# RACOON.net
KiCad netlist of a schematic drawn in EAGLE
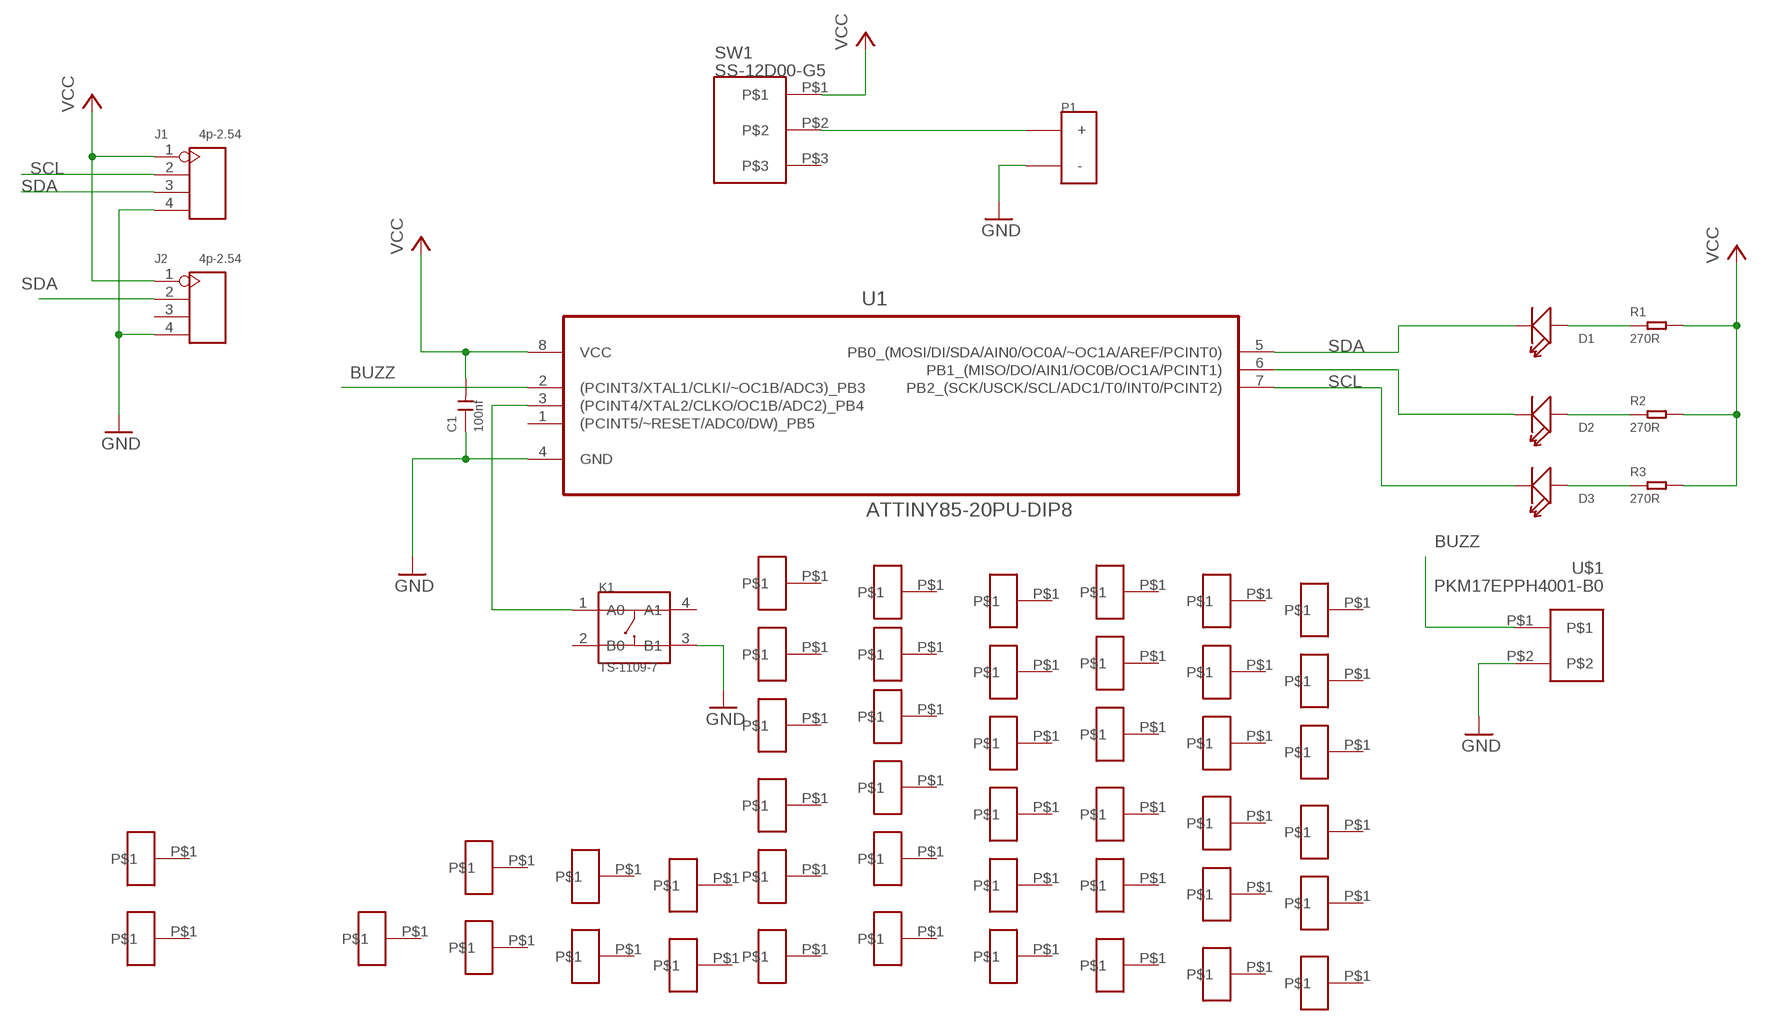
[diagram p0: schematic, sheet 1]

(export (version "E")
  (design (tool "Eeschema 10.0.6"))
  (components
    (comp (ref "C1")
      (value "100nf")
      (footprint "eagle-import:CERAMIC-2.54")
      (fields (field (name "MPN") "CC1-F5SL2A101KSPW"))
      (libsource (lib "eagle-import") (part "DIP-CERAMIC-DISC-100NF-50V-Y5V(D5.0MM)"))
    )
    (comp (ref "D1")
      (value "504BW")
      (footprint "eagle-import:LED2-2.54-D5.0MM")
      (libsource (lib "eagle-import") (part "DIP-LED-BLUE-BLUE(2P-D5MM)"))
    )
    (comp (ref "D2")
      (value "504BW")
      (footprint "eagle-import:LED2-2.54-D5.0MM")
      (libsource (lib "eagle-import") (part "DIP-LED-BLUE-BLUE(2P-D5MM)"))
    )
    (comp (ref "D3")
      (value "504BW")
      (footprint "eagle-import:LED2-2.54-D5.0MM")
      (libsource (lib "eagle-import") (part "DIP-LED-BLUE-BLUE(2P-D5MM)"))
    )
    (comp (ref "J1")
      (value "4p-2.54")
      (footprint "eagle-import:H4-2.54")
      (fields (field (name "MPN") "F185-1104A1BSYA1"))
      (libsource (lib "eagle-import") (part "DIP-BLACK-FEMALE-HEADER-VERT(4P-2.54)"))
    )
    (comp (ref "J2")
      (value "4p-2.54")
      (footprint "eagle-import:H4-2.54")
      (fields (field (name "MPN") "F185-1104A1BSYA1"))
      (libsource (lib "eagle-import") (part "DIP-BLACK-FEMALE-HEADER-VERT(4P-2.54)"))
    )
    (comp (ref "K1")
      (value "TS-1109-7")
      (footprint "eagle-import:SW4-6.2X6.2X5.0MM")
      (libsource (lib "eagle-import") (part "DIP-BUTTON-TOP-BLACK(4P-D6.2MM)"))
    )
    (comp (ref "P1")
      (value "BATTERY")
      (footprint "eagle-import:BAT_CR2450_TH_BS2450")
      (libsource (lib "eagle-import") (part "BATTERY"))
    )
    (comp (ref "R1")
      (value "270R")
      (footprint "eagle-import:PR-D2.3XL6.5MM")
      (fields (field (name "MPN") "FHCFR-1/4W-271J"))
      (libsource (lib "eagle-import") (part "DIP-RES-270R-5%-1/4W(PR-D2.3XL6.5MM)"))
    )
    (comp (ref "R2")
      (value "270R")
      (footprint "eagle-import:PR-D2.3XL6.5MM")
      (fields (field (name "MPN") "FHCFR-1/4W-271J"))
      (libsource (lib "eagle-import") (part "DIP-RES-270R-5%-1/4W(PR-D2.3XL6.5MM)"))
    )
    (comp (ref "R3")
      (value "270R")
      (footprint "eagle-import:PR-D2.3XL6.5MM")
      (fields (field (name "MPN") "FHCFR-1/4W-271J"))
      (libsource (lib "eagle-import") (part "DIP-RES-270R-5%-1/4W(PR-D2.3XL6.5MM)"))
    )
    (comp (ref "SW1")
      (value "SS-12D00-G5")
      (footprint "eagle-import:SS-12D00-G5")
      (libsource (lib "eagle-import") (part "SS-12D00-G5"))
    )
    (comp (ref "U$1")
      (value "PKM17EPPH4001-B0")
      (footprint "eagle-import:PKM17EPPH4001-B0")
      (libsource (lib "eagle-import") (part "PKM17EPPH4001-B0"))
    )
    (comp (ref "U$2")
      (value "1PIN_HOLE")
      (footprint "eagle-import:1PIN_HOLE")
      (libsource (lib "eagle-import") (part "1PIN_HOLE"))
    )
    (comp (ref "U$3")
      (value "1PIN_HOLE")
      (footprint "eagle-import:1PIN_HOLE")
      (libsource (lib "eagle-import") (part "1PIN_HOLE"))
    )
    (comp (ref "U$4")
      (value "1PIN_HOLE")
      (footprint "eagle-import:1PIN_HOLE")
      (libsource (lib "eagle-import") (part "1PIN_HOLE"))
    )
    (comp (ref "U$5")
      (value "1PIN_HOLE")
      (footprint "eagle-import:1PIN_HOLE")
      (libsource (lib "eagle-import") (part "1PIN_HOLE"))
    )
    (comp (ref "U$6")
      (value "1PIN_HOLE")
      (footprint "eagle-import:1PIN_HOLE")
      (libsource (lib "eagle-import") (part "1PIN_HOLE"))
    )
    (comp (ref "U$7")
      (value "1PIN_HOLE")
      (footprint "eagle-import:1PIN_HOLE")
      (libsource (lib "eagle-import") (part "1PIN_HOLE"))
    )
    (comp (ref "U$8")
      (value "1PIN_HOLE")
      (footprint "eagle-import:1PIN_HOLE")
      (libsource (lib "eagle-import") (part "1PIN_HOLE"))
    )
    (comp (ref "U$9")
      (value "1PIN_HOLE")
      (footprint "eagle-import:1PIN_HOLE")
      (libsource (lib "eagle-import") (part "1PIN_HOLE"))
    )
    (comp (ref "U$10")
      (value "1PIN_HOLE")
      (footprint "eagle-import:1PIN_HOLE")
      (libsource (lib "eagle-import") (part "1PIN_HOLE"))
    )
    (comp (ref "U$11")
      (value "1PIN_HOLE")
      (footprint "eagle-import:1PIN_HOLE")
      (libsource (lib "eagle-import") (part "1PIN_HOLE"))
    )
    (comp (ref "U$12")
      (value "1PIN_HOLE")
      (footprint "eagle-import:1PIN_HOLE")
      (libsource (lib "eagle-import") (part "1PIN_HOLE"))
    )
    (comp (ref "U$13")
      (value "1PIN_HOLE")
      (footprint "eagle-import:1PIN_HOLE")
      (libsource (lib "eagle-import") (part "1PIN_HOLE"))
    )
    (comp (ref "U$14")
      (value "1PIN_HOLE")
      (footprint "eagle-import:1PIN_HOLE")
      (libsource (lib "eagle-import") (part "1PIN_HOLE"))
    )
    (comp (ref "U$15")
      (value "1PIN_HOLE")
      (footprint "eagle-import:1PIN_HOLE")
      (libsource (lib "eagle-import") (part "1PIN_HOLE"))
    )
    (comp (ref "U$16")
      (value "1PIN_HOLE")
      (footprint "eagle-import:1PIN_HOLE")
      (libsource (lib "eagle-import") (part "1PIN_HOLE"))
    )
    (comp (ref "U$17")
      (value "1PIN_HOLE")
      (footprint "eagle-import:1PIN_HOLE")
      (libsource (lib "eagle-import") (part "1PIN_HOLE"))
    )
    (comp (ref "U$18")
      (value "1PIN_HOLE")
      (footprint "eagle-import:1PIN_HOLE")
      (libsource (lib "eagle-import") (part "1PIN_HOLE"))
    )
    (comp (ref "U$19")
      (value "1PIN_HOLE")
      (footprint "eagle-import:1PIN_HOLE")
      (libsource (lib "eagle-import") (part "1PIN_HOLE"))
    )
    (comp (ref "U$20")
      (value "1PIN_HOLE")
      (footprint "eagle-import:1PIN_HOLE")
      (libsource (lib "eagle-import") (part "1PIN_HOLE"))
    )
    (comp (ref "U$21")
      (value "1PIN_HOLE")
      (footprint "eagle-import:1PIN_HOLE")
      (libsource (lib "eagle-import") (part "1PIN_HOLE"))
    )
    (comp (ref "U$22")
      (value "1PIN_HOLE")
      (footprint "eagle-import:1PIN_HOLE")
      (libsource (lib "eagle-import") (part "1PIN_HOLE"))
    )
    (comp (ref "U$23")
      (value "1PIN_HOLE")
      (footprint "eagle-import:1PIN_HOLE")
      (libsource (lib "eagle-import") (part "1PIN_HOLE"))
    )
    (comp (ref "U$24")
      (value "1PIN_HOLE")
      (footprint "eagle-import:1PIN_HOLE")
      (libsource (lib "eagle-import") (part "1PIN_HOLE"))
    )
    (comp (ref "U$25")
      (value "1PIN_HOLE")
      (footprint "eagle-import:1PIN_HOLE")
      (libsource (lib "eagle-import") (part "1PIN_HOLE"))
    )
    (comp (ref "U$26")
      (value "1PIN_HOLE")
      (footprint "eagle-import:1PIN_HOLE")
      (libsource (lib "eagle-import") (part "1PIN_HOLE"))
    )
    (comp (ref "U$27")
      (value "1PIN_HOLE")
      (footprint "eagle-import:1PIN_HOLE")
      (libsource (lib "eagle-import") (part "1PIN_HOLE"))
    )
    (comp (ref "U$28")
      (value "1PIN_HOLE")
      (footprint "eagle-import:1PIN_HOLE")
      (libsource (lib "eagle-import") (part "1PIN_HOLE"))
    )
    (comp (ref "U$29")
      (value "1PIN_HOLE")
      (footprint "eagle-import:1PIN_HOLE")
      (libsource (lib "eagle-import") (part "1PIN_HOLE"))
    )
    (comp (ref "U$30")
      (value "1PIN_HOLE")
      (footprint "eagle-import:1PIN_HOLE")
      (libsource (lib "eagle-import") (part "1PIN_HOLE"))
    )
    (comp (ref "U$31")
      (value "1PIN_HOLE")
      (footprint "eagle-import:1PIN_HOLE")
      (libsource (lib "eagle-import") (part "1PIN_HOLE"))
    )
    (comp (ref "U$32")
      (value "1PIN_HOLE")
      (footprint "eagle-import:1PIN_HOLE")
      (libsource (lib "eagle-import") (part "1PIN_HOLE"))
    )
    (comp (ref "U$33")
      (value "1PIN_HOLE")
      (footprint "eagle-import:1PIN_HOLE")
      (libsource (lib "eagle-import") (part "1PIN_HOLE"))
    )
    (comp (ref "U$34")
      (value "1PIN_HOLE")
      (footprint "eagle-import:1PIN_HOLE")
      (libsource (lib "eagle-import") (part "1PIN_HOLE"))
    )
    (comp (ref "U$35")
      (value "1PIN_HOLE")
      (footprint "eagle-import:1PIN_HOLE")
      (libsource (lib "eagle-import") (part "1PIN_HOLE"))
    )
    (comp (ref "U$36")
      (value "1PIN_HOLE")
      (footprint "eagle-import:1PIN_HOLE")
      (libsource (lib "eagle-import") (part "1PIN_HOLE"))
    )
    (comp (ref "U$37")
      (value "1PIN_HOLE")
      (footprint "eagle-import:1PIN_HOLE")
      (libsource (lib "eagle-import") (part "1PIN_HOLE"))
    )
    (comp (ref "U$41")
      (value "1PIN_HOLE")
      (footprint "eagle-import:1PIN_HOLE")
      (libsource (lib "eagle-import") (part "1PIN_HOLE"))
    )
    (comp (ref "U$42")
      (value "1PIN_HOLE")
      (footprint "eagle-import:1PIN_HOLE")
      (libsource (lib "eagle-import") (part "1PIN_HOLE"))
    )
    (comp (ref "U$43")
      (value "1PIN_HOLE")
      (footprint "eagle-import:1PIN_HOLE")
      (libsource (lib "eagle-import") (part "1PIN_HOLE"))
    )
    (comp (ref "U$44")
      (value "1PIN_HOLE")
      (footprint "eagle-import:1PIN_HOLE")
      (libsource (lib "eagle-import") (part "1PIN_HOLE"))
    )
    (comp (ref "U$45")
      (value "1PIN_HOLE")
      (footprint "eagle-import:1PIN_HOLE")
      (libsource (lib "eagle-import") (part "1PIN_HOLE"))
    )
    (comp (ref "U$46")
      (value "1PIN_HOLE")
      (footprint "eagle-import:1PIN_HOLE")
      (libsource (lib "eagle-import") (part "1PIN_HOLE"))
    )
    (comp (ref "U$47")
      (value "1PIN_HOLE")
      (footprint "eagle-import:1PIN_HOLE")
      (libsource (lib "eagle-import") (part "1PIN_HOLE"))
    )
    (comp (ref "U$49")
      (value "1PIN_HOLE")
      (footprint "eagle-import:1PIN_HOLE")
      (libsource (lib "eagle-import") (part "1PIN_HOLE"))
    )
    (comp (ref "U$50")
      (value "1PIN_HOLE")
      (footprint "eagle-import:1PIN_HOLE")
      (libsource (lib "eagle-import") (part "1PIN_HOLE"))
    )
    (comp (ref "U1")
      (value "ATTINY85-20PU-DIP8")
      (footprint "eagle-import:DIP254P762X533-8")
      (fields (field (name "MPN") "ATTINY85-20PU"))
      (libsource (lib "eagle-import") (part "MCU-ATTINY85-20PU(DIP8)1"))
    )
  )
  (nets
    (net (code "1") (name "/BUZZ") (class "Default")
      (node (ref "U$1") (pin "P$1") (pinfunction "P$1_P$1") (pintype "bidirectional"))
      (node (ref "U1") (pin "2") (pinfunction "(PCINT3/XTAL1/CLKI/~{OC1B/ADC3})_PB3_2") (pintype "bidirectional"))
    )
    (net (code "2") (name "/SCL") (class "Default")
      (node (ref "D3") (pin "-") (pinfunction "-_-") (pintype "passive"))
      (node (ref "J1") (pin "2") (pinfunction "P$2_2") (pintype "bidirectional"))
      (node (ref "U1") (pin "7") (pinfunction "PB2_(SCK/USCK/SCL/ADC1/T0/INT0/PCINT2)_7") (pintype "bidirectional"))
    )
    (net (code "3") (name "/SDA") (class "Default")
      (node (ref "D1") (pin "-") (pinfunction "-_-") (pintype "passive"))
      (node (ref "J1") (pin "3") (pinfunction "P$3_3") (pintype "bidirectional"))
      (node (ref "J2") (pin "2") (pinfunction "P$2_2") (pintype "bidirectional"))
      (node (ref "U1") (pin "5") (pinfunction "PB0_(MOSI/DI/SDA/AIN0/OC0A/~{OC1A/AREF/PCINT0})_5") (pintype "bidirectional"))
    )
    (net (code "4") (name "GND") (class "Default")
      (node (ref "C1") (pin "1") (pinfunction "1_1") (pintype "passive"))
      (node (ref "J1") (pin "4") (pinfunction "P$4_4") (pintype "bidirectional"))
      (node (ref "J2") (pin "4") (pinfunction "P$4_4") (pintype "bidirectional"))
      (node (ref "K1") (pin "3") (pinfunction "B1_3") (pintype "bidirectional"))
      (node (ref "P1") (pin "-") (pinfunction "-_-") (pintype "power_in"))
      (node (ref "U$1") (pin "P$2") (pinfunction "P$2_P$2") (pintype "bidirectional"))
      (node (ref "U1") (pin "4") (pinfunction "GND_4") (pintype "passive"))
    )
    (net (code "5") (name "Net-(D1-Pad+)") (class "Default")
      (node (ref "D1") (pin "+") (pinfunction "+_+") (pintype "passive"))
      (node (ref "R1") (pin "1") (pinfunction "1_1") (pintype "passive"))
    )
    (net (code "6") (name "Net-(D2-Pad+)") (class "Default")
      (node (ref "D2") (pin "+") (pinfunction "+_+") (pintype "passive"))
      (node (ref "R2") (pin "1") (pinfunction "1_1") (pintype "passive"))
    )
    (net (code "7") (name "Net-(D3-Pad+)") (class "Default")
      (node (ref "D3") (pin "+") (pinfunction "+_+") (pintype "passive"))
      (node (ref "R3") (pin "1") (pinfunction "1_1") (pintype "passive"))
    )
    (net (code "8") (name "Net-(K1-A0)") (class "Default")
      (node (ref "K1") (pin "1") (pinfunction "A0_1") (pintype "bidirectional"))
      (node (ref "U1") (pin "3") (pinfunction "(PCINT4/XTAL2/CLKO/OC1B/ADC2)_PB4_3") (pintype "bidirectional"))
    )
    (net (code "9") (name "Net-(P1-Pad+)") (class "Default")
      (node (ref "P1") (pin "+") (pinfunction "+_+") (pintype "power_in"))
      (node (ref "SW1") (pin "P$2") (pinfunction "P$2_P$2") (pintype "bidirectional"))
    )
    (net (code "10") (name "Net-(U1-PB1_(MISO{slash}DO{slash}AIN1{slash}OC0B{slash}OC1A{slash}PCINT1))") (class "Default")
      (node (ref "D2") (pin "-") (pinfunction "-_-") (pintype "passive"))
      (node (ref "U1") (pin "6") (pinfunction "PB1_(MISO/DO/AIN1/OC0B/OC1A/PCINT1)_6") (pintype "bidirectional"))
    )
    (net (code "11") (name "VCC") (class "Default")
      (node (ref "C1") (pin "2") (pinfunction "2_2") (pintype "passive"))
      (node (ref "J1") (pin "1") (pinfunction "P$1_1") (pintype "bidirectional"))
      (node (ref "J2") (pin "1") (pinfunction "P$1_1") (pintype "bidirectional"))
      (node (ref "R1") (pin "2") (pinfunction "2_2") (pintype "passive"))
      (node (ref "R2") (pin "2") (pinfunction "2_2") (pintype "passive"))
      (node (ref "R3") (pin "2") (pinfunction "2_2") (pintype "passive"))
      (node (ref "SW1") (pin "P$1") (pinfunction "P$1_P$1") (pintype "bidirectional"))
      (node (ref "U1") (pin "8") (pinfunction "VCC_8") (pintype "power_in"))
    )
    (net (code "12") (name "unconnected-(J2-P$3-Pad3)") (class "Default")
      (node (ref "J2") (pin "3") (pinfunction "P$3_3") (pintype "bidirectional"))
    )
    (net (code "13") (name "unconnected-(K1-A1-Pad4)") (class "Default")
      (node (ref "K1") (pin "4") (pinfunction "A1_4") (pintype "bidirectional"))
    )
    (net (code "14") (name "unconnected-(K1-B0-Pad2)") (class "Default")
      (node (ref "K1") (pin "2") (pinfunction "B0_2") (pintype "bidirectional"))
    )
    (net (code "15") (name "unconnected-(SW1-PadP$3)") (class "Default")
      (node (ref "SW1") (pin "P$3") (pinfunction "P$3_P$3") (pintype "bidirectional"))
    )
    (net (code "16") (name "unconnected-(U$2-PadP$1)") (class "Default")
      (node (ref "U$2") (pin "P$1") (pinfunction "P$1_P$1") (pintype "bidirectional"))
    )
    (net (code "17") (name "unconnected-(U$3-PadP$1)") (class "Default")
      (node (ref "U$3") (pin "P$1") (pinfunction "P$1_P$1") (pintype "bidirectional"))
    )
    (net (code "18") (name "unconnected-(U$4-PadP$1)") (class "Default")
      (node (ref "U$4") (pin "P$1") (pinfunction "P$1_P$1") (pintype "bidirectional"))
    )
    (net (code "19") (name "unconnected-(U$5-PadP$1)") (class "Default")
      (node (ref "U$5") (pin "P$1") (pinfunction "P$1_P$1") (pintype "bidirectional"))
    )
    (net (code "20") (name "unconnected-(U$6-PadP$1)") (class "Default")
      (node (ref "U$6") (pin "P$1") (pinfunction "P$1_P$1") (pintype "bidirectional"))
    )
    (net (code "21") (name "unconnected-(U$7-PadP$1)") (class "Default")
      (node (ref "U$7") (pin "P$1") (pinfunction "P$1_P$1") (pintype "bidirectional"))
    )
    (net (code "22") (name "unconnected-(U$8-PadP$1)") (class "Default")
      (node (ref "U$8") (pin "P$1") (pinfunction "P$1_P$1") (pintype "bidirectional"))
    )
    (net (code "23") (name "unconnected-(U$9-PadP$1)") (class "Default")
      (node (ref "U$9") (pin "P$1") (pinfunction "P$1_P$1") (pintype "bidirectional"))
    )
    (net (code "24") (name "unconnected-(U$10-PadP$1)") (class "Default")
      (node (ref "U$10") (pin "P$1") (pinfunction "P$1_P$1") (pintype "bidirectional"))
    )
    (net (code "25") (name "unconnected-(U$11-PadP$1)") (class "Default")
      (node (ref "U$11") (pin "P$1") (pinfunction "P$1_P$1") (pintype "bidirectional"))
    )
    (net (code "26") (name "unconnected-(U$12-PadP$1)") (class "Default")
      (node (ref "U$12") (pin "P$1") (pinfunction "P$1_P$1") (pintype "bidirectional"))
    )
    (net (code "27") (name "unconnected-(U$13-PadP$1)") (class "Default")
      (node (ref "U$13") (pin "P$1") (pinfunction "P$1_P$1") (pintype "bidirectional"))
    )
    (net (code "28") (name "unconnected-(U$14-PadP$1)") (class "Default")
      (node (ref "U$14") (pin "P$1") (pinfunction "P$1_P$1") (pintype "bidirectional"))
    )
    (net (code "29") (name "unconnected-(U$15-PadP$1)") (class "Default")
      (node (ref "U$15") (pin "P$1") (pinfunction "P$1_P$1") (pintype "bidirectional"))
    )
    (net (code "30") (name "unconnected-(U$16-PadP$1)") (class "Default")
      (node (ref "U$16") (pin "P$1") (pinfunction "P$1_P$1") (pintype "bidirectional"))
    )
    (net (code "31") (name "unconnected-(U$17-PadP$1)") (class "Default")
      (node (ref "U$17") (pin "P$1") (pinfunction "P$1_P$1") (pintype "bidirectional"))
    )
    (net (code "32") (name "unconnected-(U$18-PadP$1)") (class "Default")
      (node (ref "U$18") (pin "P$1") (pinfunction "P$1_P$1") (pintype "bidirectional"))
    )
    (net (code "33") (name "unconnected-(U$19-PadP$1)") (class "Default")
      (node (ref "U$19") (pin "P$1") (pinfunction "P$1_P$1") (pintype "bidirectional"))
    )
    (net (code "34") (name "unconnected-(U$20-PadP$1)") (class "Default")
      (node (ref "U$20") (pin "P$1") (pinfunction "P$1_P$1") (pintype "bidirectional"))
    )
    (net (code "35") (name "unconnected-(U$21-PadP$1)") (class "Default")
      (node (ref "U$21") (pin "P$1") (pinfunction "P$1_P$1") (pintype "bidirectional"))
    )
    (net (code "36") (name "unconnected-(U$22-PadP$1)") (class "Default")
      (node (ref "U$22") (pin "P$1") (pinfunction "P$1_P$1") (pintype "bidirectional"))
    )
    (net (code "37") (name "unconnected-(U$23-PadP$1)") (class "Default")
      (node (ref "U$23") (pin "P$1") (pinfunction "P$1_P$1") (pintype "bidirectional"))
    )
    (net (code "38") (name "unconnected-(U$24-PadP$1)") (class "Default")
      (node (ref "U$24") (pin "P$1") (pinfunction "P$1_P$1") (pintype "bidirectional"))
    )
    (net (code "39") (name "unconnected-(U$25-PadP$1)") (class "Default")
      (node (ref "U$25") (pin "P$1") (pinfunction "P$1_P$1") (pintype "bidirectional"))
    )
    (net (code "40") (name "unconnected-(U$26-PadP$1)") (class "Default")
      (node (ref "U$26") (pin "P$1") (pinfunction "P$1_P$1") (pintype "bidirectional"))
    )
    (net (code "41") (name "unconnected-(U$27-PadP$1)") (class "Default")
      (node (ref "U$27") (pin "P$1") (pinfunction "P$1_P$1") (pintype "bidirectional"))
    )
    (net (code "42") (name "unconnected-(U$28-PadP$1)") (class "Default")
      (node (ref "U$28") (pin "P$1") (pinfunction "P$1_P$1") (pintype "bidirectional"))
    )
    (net (code "43") (name "unconnected-(U$29-PadP$1)") (class "Default")
      (node (ref "U$29") (pin "P$1") (pinfunction "P$1_P$1") (pintype "bidirectional"))
    )
    (net (code "44") (name "unconnected-(U$30-PadP$1)") (class "Default")
      (node (ref "U$30") (pin "P$1") (pinfunction "P$1_P$1") (pintype "bidirectional"))
    )
    (net (code "45") (name "unconnected-(U$31-PadP$1)") (class "Default")
      (node (ref "U$31") (pin "P$1") (pinfunction "P$1_P$1") (pintype "bidirectional"))
    )
    (net (code "46") (name "unconnected-(U$32-PadP$1)") (class "Default")
      (node (ref "U$32") (pin "P$1") (pinfunction "P$1_P$1") (pintype "bidirectional"))
    )
    (net (code "47") (name "unconnected-(U$33-PadP$1)") (class "Default")
      (node (ref "U$33") (pin "P$1") (pinfunction "P$1_P$1") (pintype "bidirectional"))
    )
    (net (code "48") (name "unconnected-(U$34-PadP$1)") (class "Default")
      (node (ref "U$34") (pin "P$1") (pinfunction "P$1_P$1") (pintype "bidirectional"))
    )
    (net (code "49") (name "unconnected-(U$35-PadP$1)") (class "Default")
      (node (ref "U$35") (pin "P$1") (pinfunction "P$1_P$1") (pintype "bidirectional"))
    )
    (net (code "50") (name "unconnected-(U$36-PadP$1)") (class "Default")
      (node (ref "U$36") (pin "P$1") (pinfunction "P$1_P$1") (pintype "bidirectional"))
    )
    (net (code "51") (name "unconnected-(U$37-PadP$1)") (class "Default")
      (node (ref "U$37") (pin "P$1") (pinfunction "P$1_P$1") (pintype "bidirectional"))
    )
    (net (code "52") (name "unconnected-(U$41-PadP$1)") (class "Default")
      (node (ref "U$41") (pin "P$1") (pinfunction "P$1_P$1") (pintype "bidirectional"))
    )
    (net (code "53") (name "unconnected-(U$42-PadP$1)") (class "Default")
      (node (ref "U$42") (pin "P$1") (pinfunction "P$1_P$1") (pintype "bidirectional"))
    )
    (net (code "54") (name "unconnected-(U$43-PadP$1)") (class "Default")
      (node (ref "U$43") (pin "P$1") (pinfunction "P$1_P$1") (pintype "bidirectional"))
    )
    (net (code "55") (name "unconnected-(U$44-PadP$1)") (class "Default")
      (node (ref "U$44") (pin "P$1") (pinfunction "P$1_P$1") (pintype "bidirectional"))
    )
    (net (code "56") (name "unconnected-(U$45-PadP$1)") (class "Default")
      (node (ref "U$45") (pin "P$1") (pinfunction "P$1_P$1") (pintype "bidirectional"))
    )
    (net (code "57") (name "unconnected-(U$46-PadP$1)") (class "Default")
      (node (ref "U$46") (pin "P$1") (pinfunction "P$1_P$1") (pintype "bidirectional"))
    )
    (net (code "58") (name "unconnected-(U$47-PadP$1)") (class "Default")
      (node (ref "U$47") (pin "P$1") (pinfunction "P$1_P$1") (pintype "bidirectional"))
    )
    (net (code "59") (name "unconnected-(U$49-PadP$1)") (class "Default")
      (node (ref "U$49") (pin "P$1") (pinfunction "P$1_P$1") (pintype "bidirectional"))
    )
    (net (code "60") (name "unconnected-(U$50-PadP$1)") (class "Default")
      (node (ref "U$50") (pin "P$1") (pinfunction "P$1_P$1") (pintype "bidirectional"))
    )
    (net (code "61") (name "unconnected-(U1-(PCINT5{slash}~{RESET{slash}ADC0{slash}DW})_PB5-Pad1)") (class "Default")
      (node (ref "U1") (pin "1") (pinfunction "(PCINT5/~{RESET/ADC0/DW})_PB5_1") (pintype "bidirectional"))
    )
  )
)
